# Carrier_Board.net
KiCad netlist of a schematic drawn in EAGLE
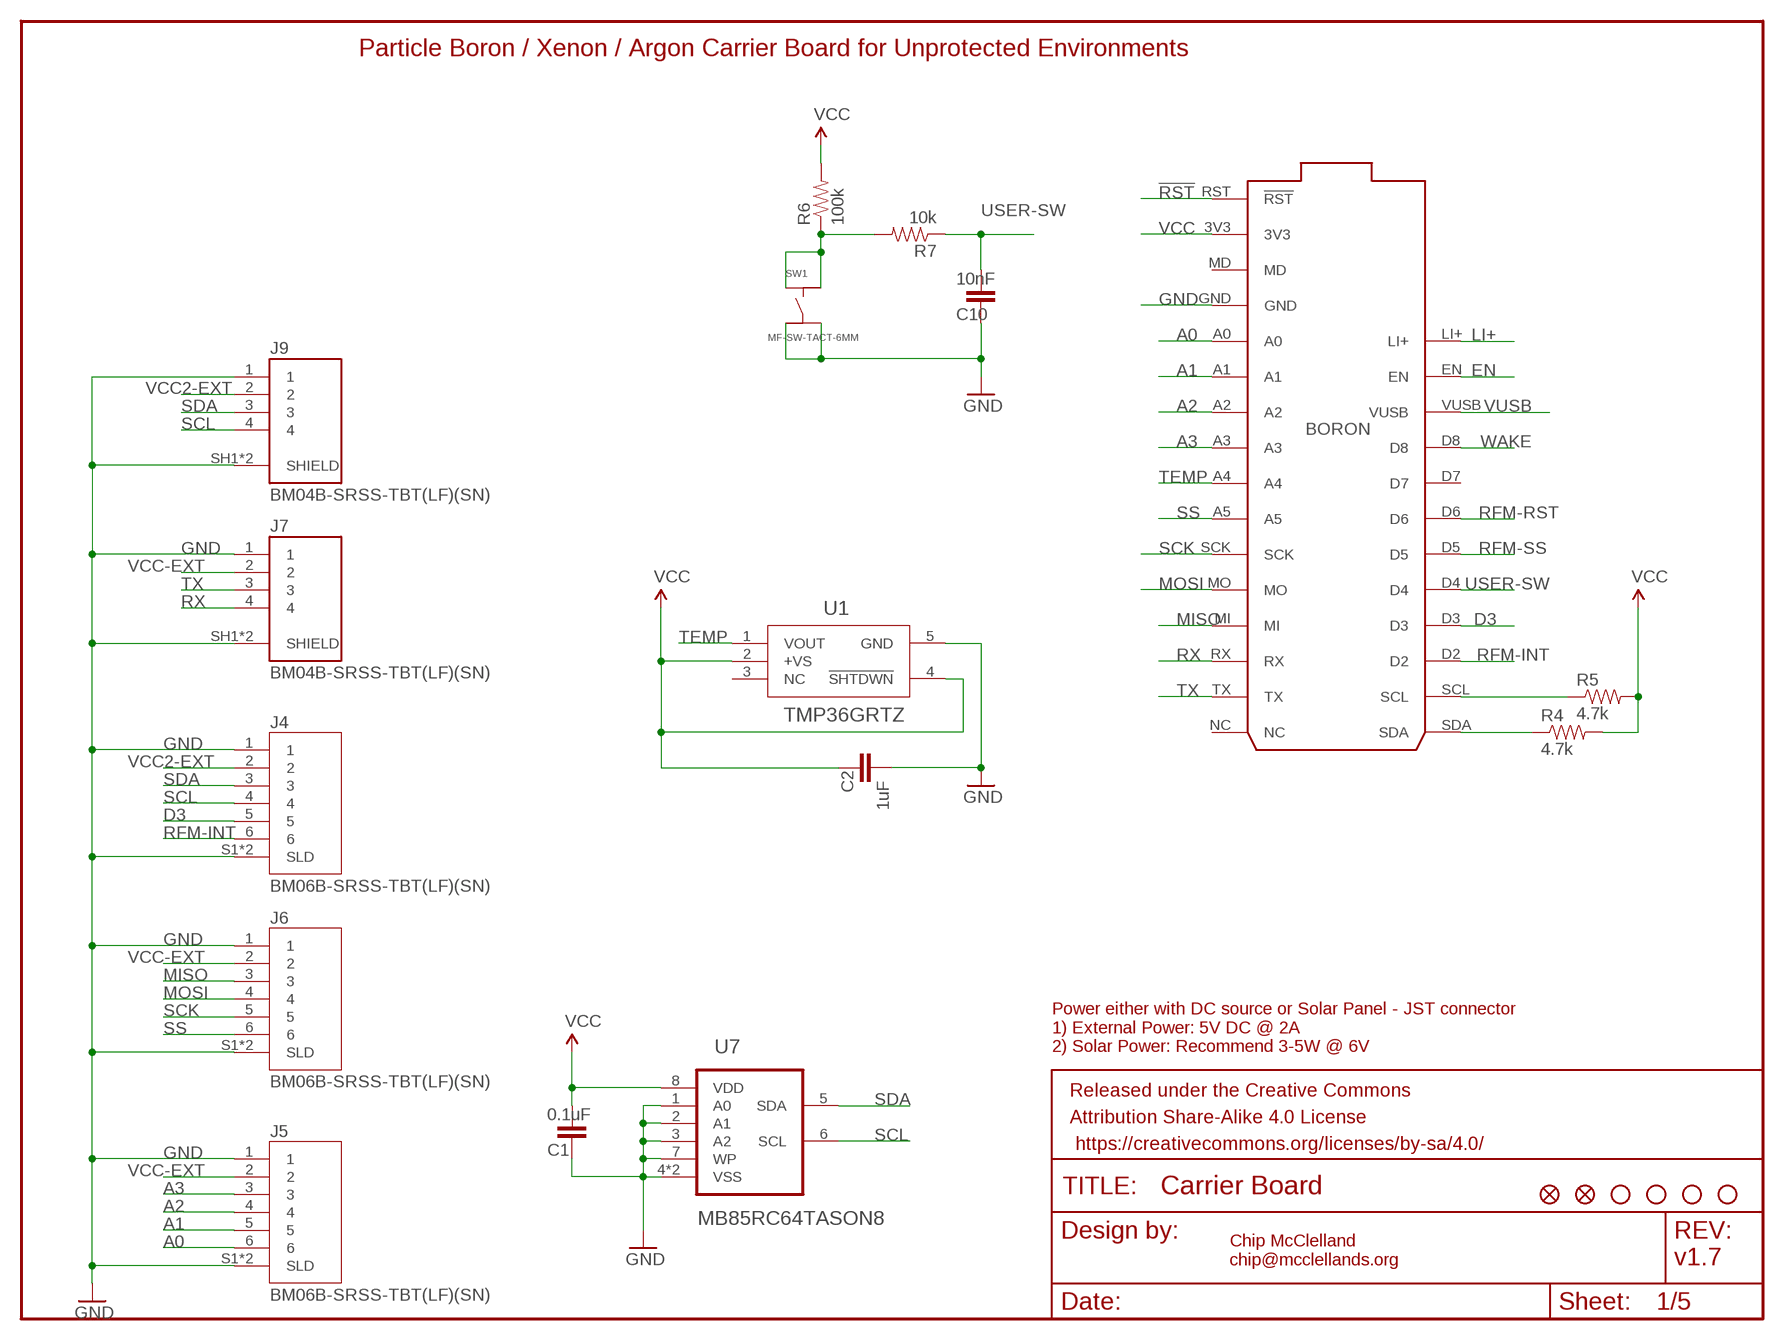
[diagram p0: schematic, sheet 1]
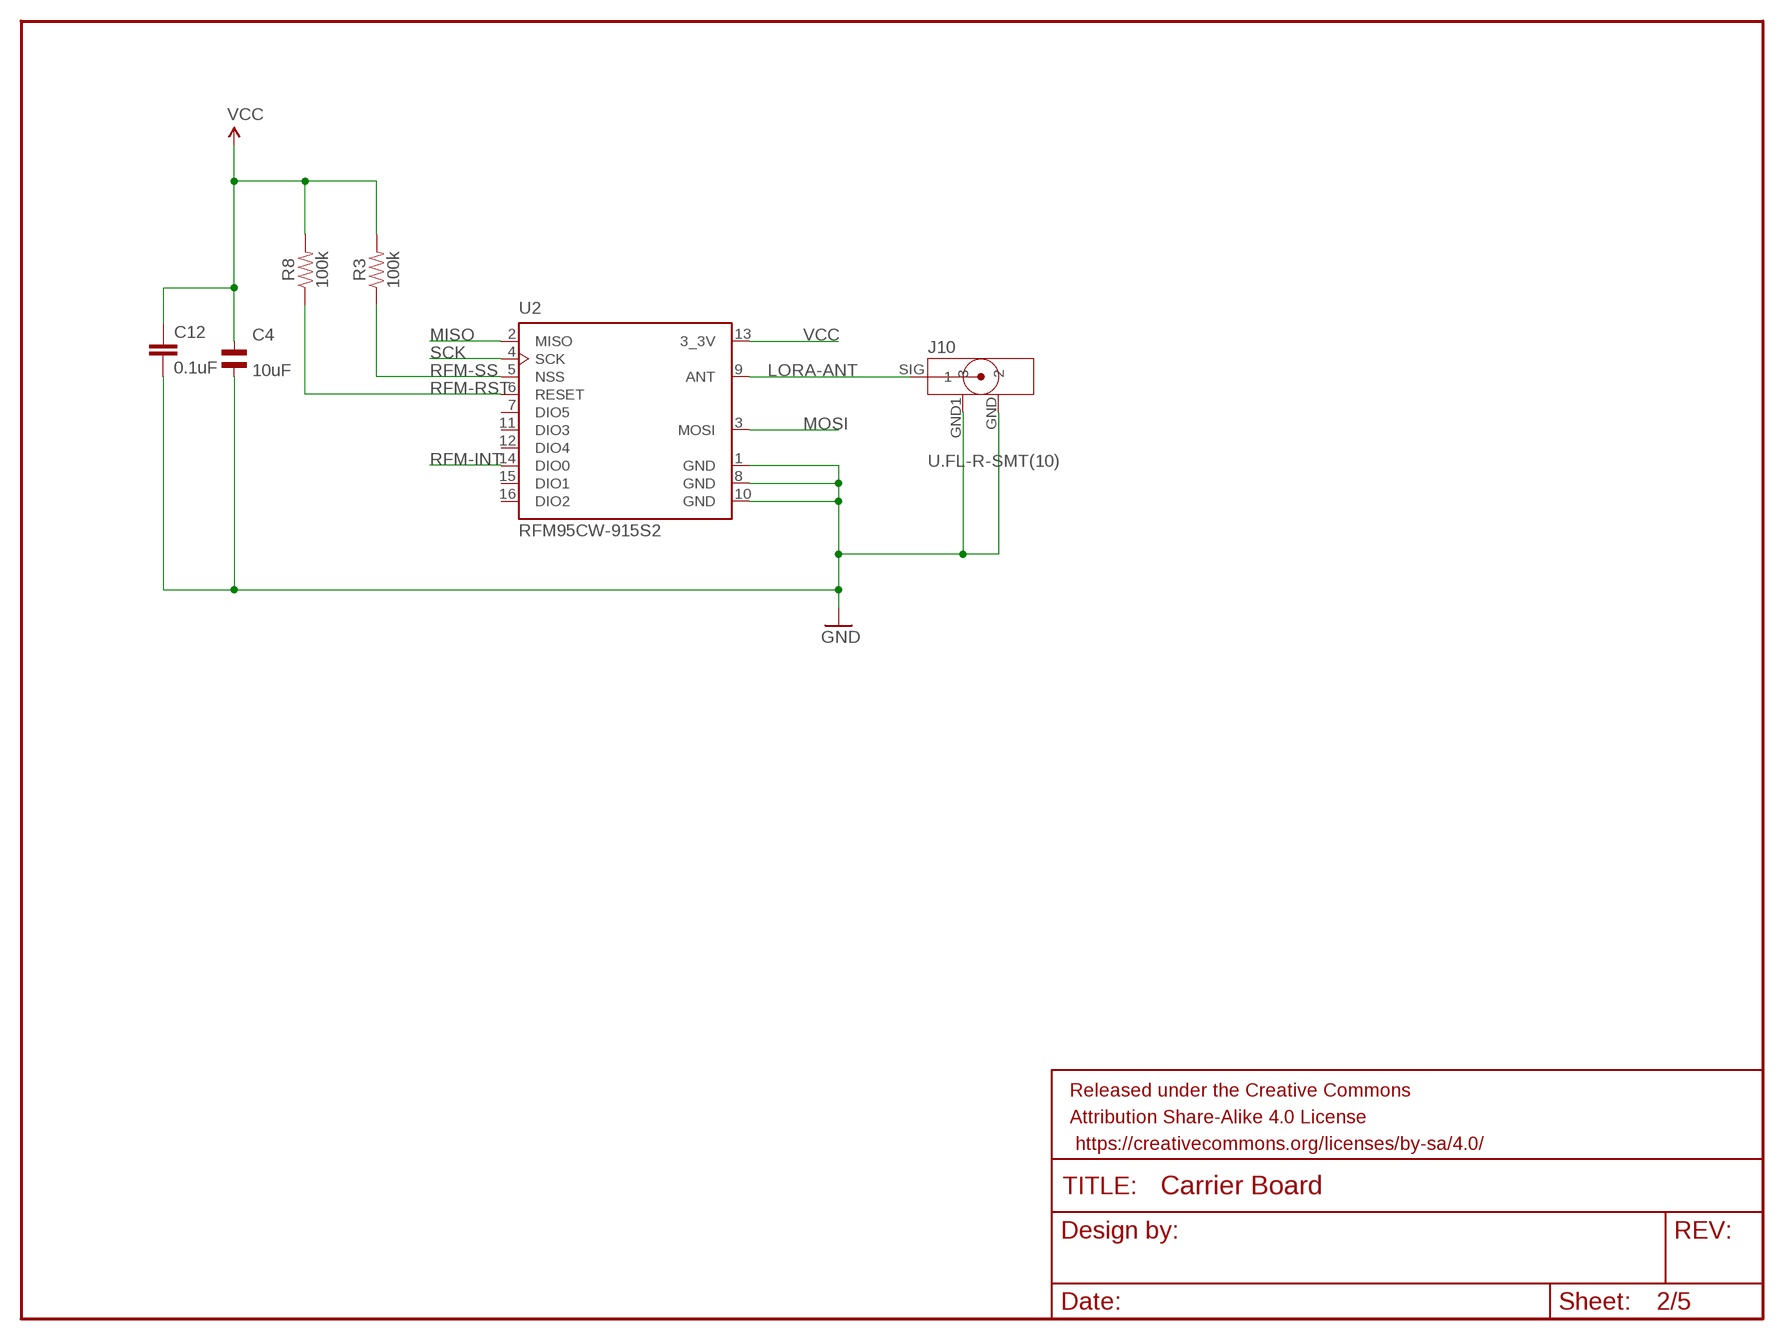
[diagram p1: schematic, sheet 2]
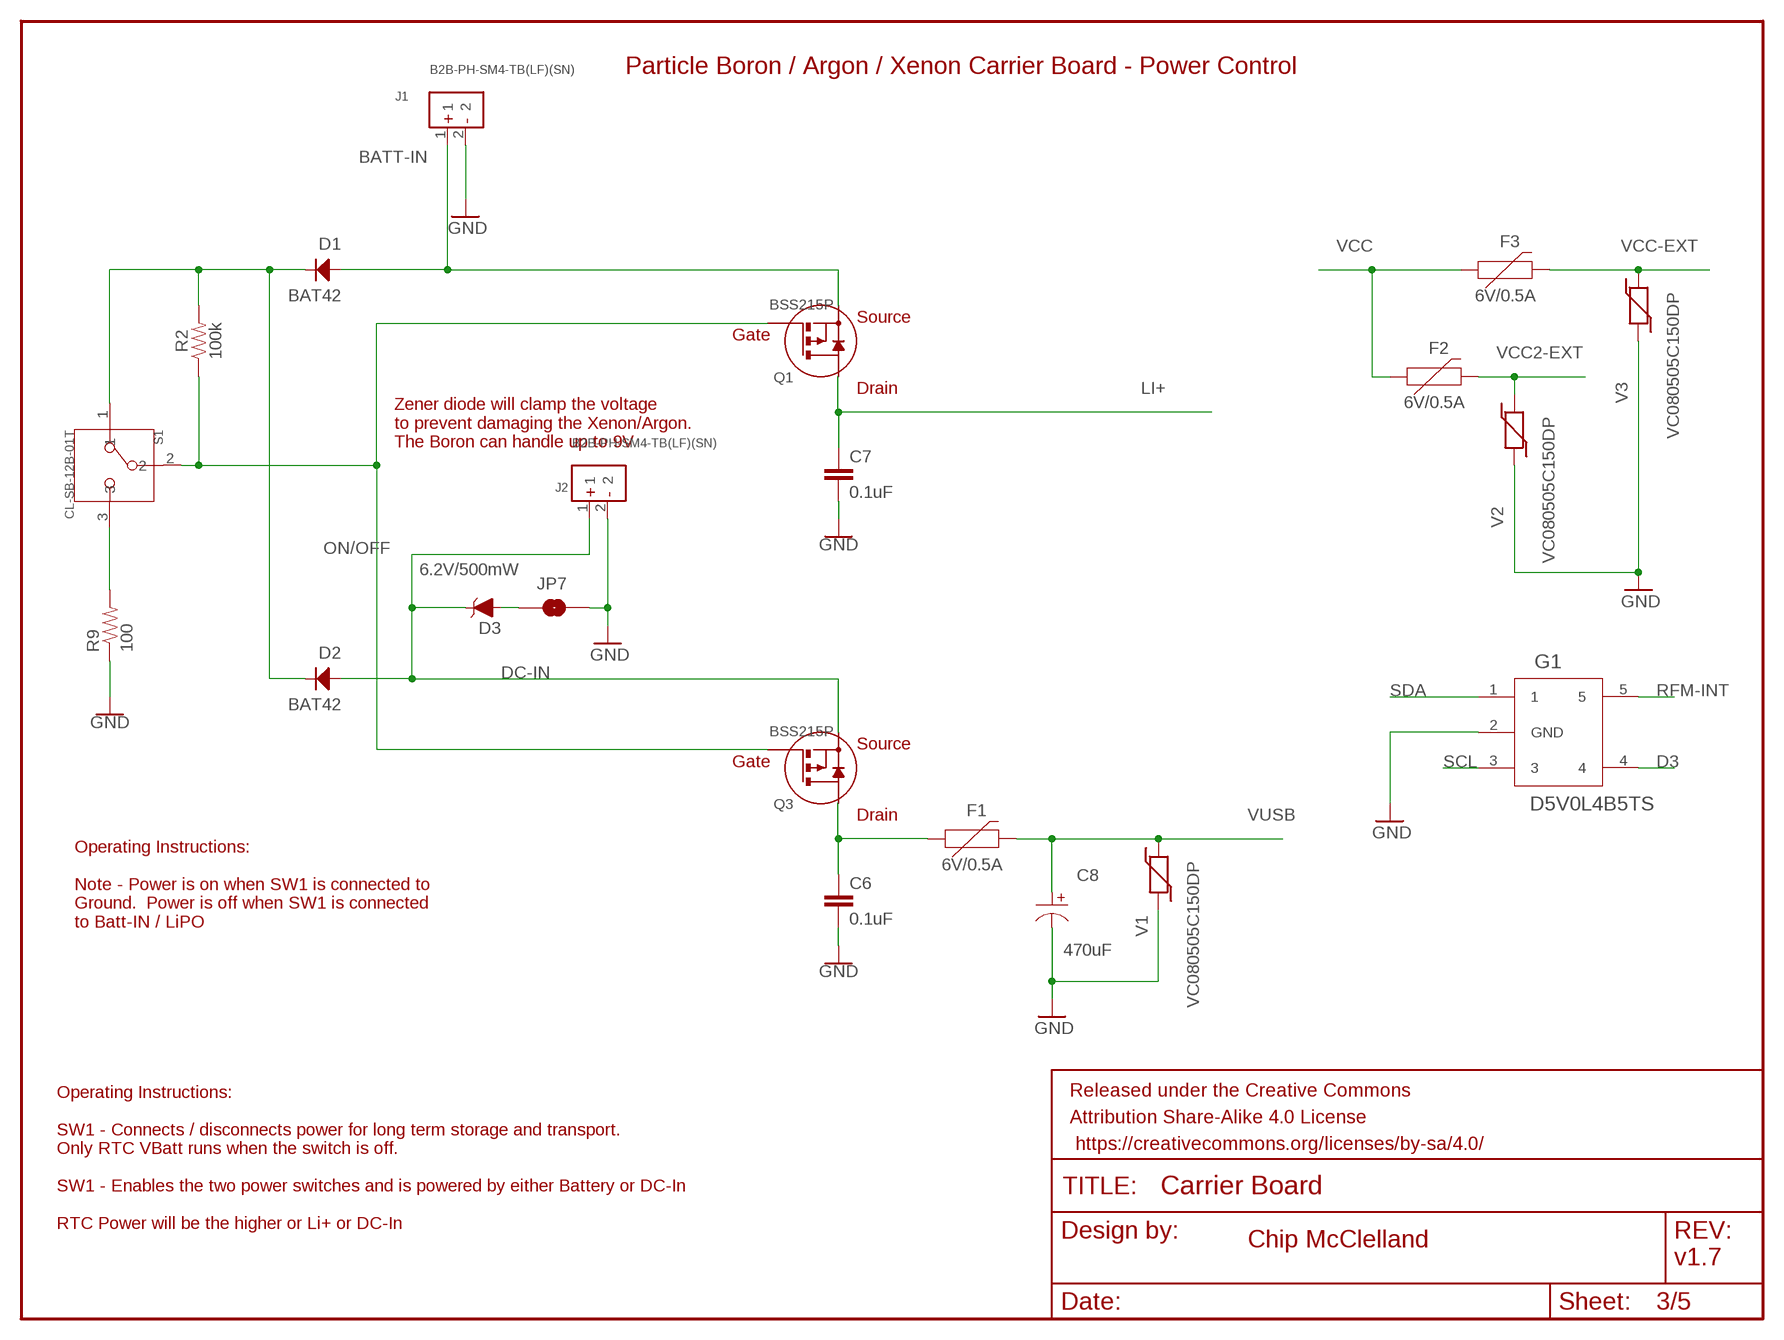
[diagram p2: schematic, sheet 3]
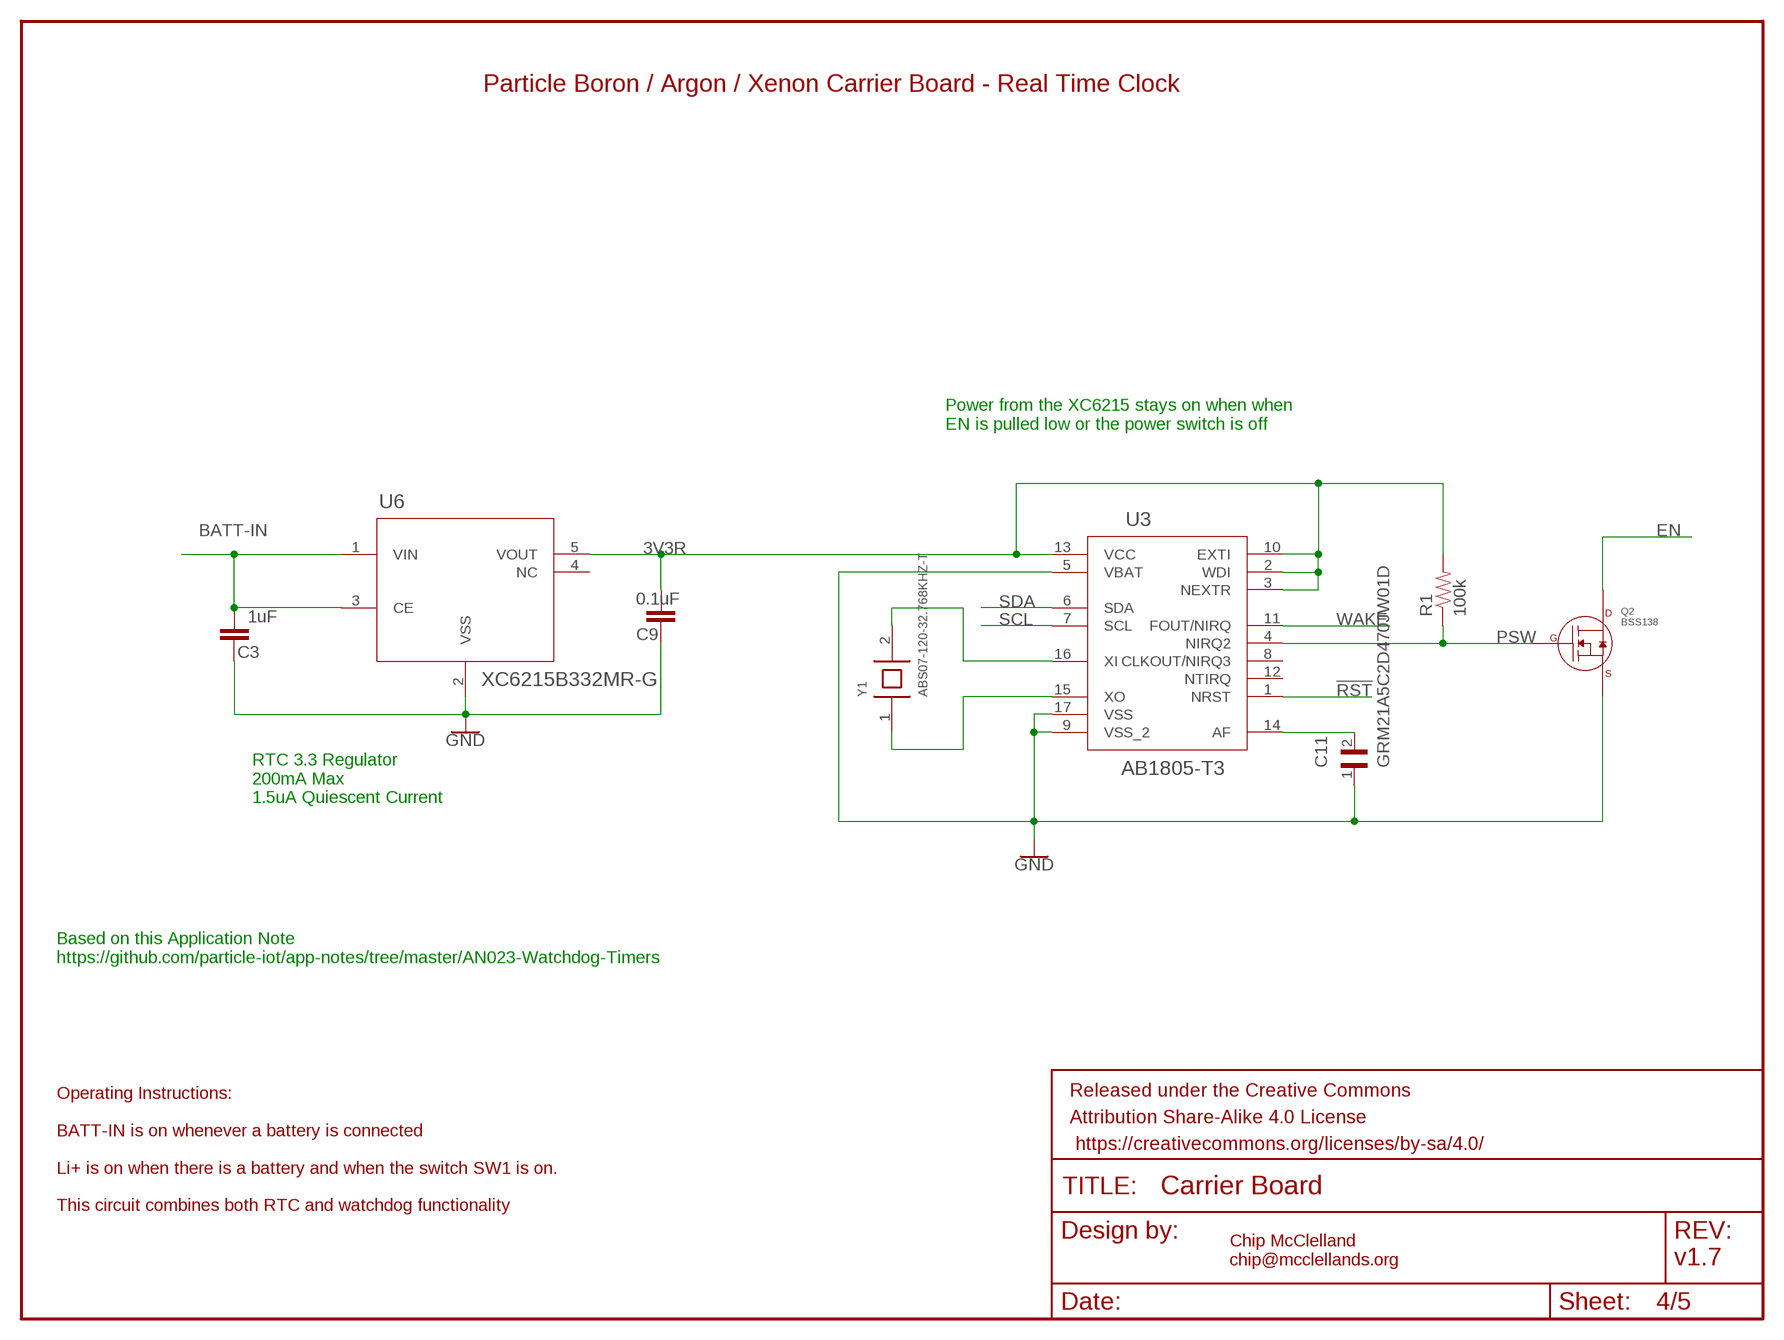
[diagram p3: schematic, sheet 4]
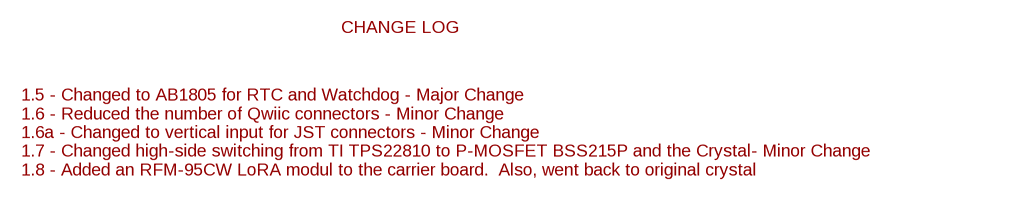
[diagram p4: schematic, sheet 5]

(export (version "E")
  (design (tool "Eeschema 10.0.6"))
  (components
    (comp (ref "C4")
      (value "10uF")
      (footprint "eagle-import:C1206")
      (fields
        (field (name "HOUSEPART") "Yes")
        (field (name "MPN") "MF-CAP-1206-10uF")
        (field (name "VOLTAGE") "16V")
      )
      (libsource (lib "eagle-import") (part "CAP-MF-10UF-1206"))
    )
    (comp (ref "C12")
      (value "0.1uF")
      (footprint "eagle-import:0805@1")
      (fields
        (field (name "HOUSEPART") "YES")
        (field (name "MPN") "MF-CAP-0805-0.1uF")
        (field (name "HOUSEPART_1") "Yes")
      )
      (libsource (lib "eagle-import") (part "CAP-MF-0.1UF-0805"))
    )
    (comp (ref "FRAME4")
      (value "FRAME-LETTERNO_PACKAGE")
      (footprint "eagle-import:DUMMY")
      (fields (field (name "DESIGNER") "Nobody"))
      (libsource (lib "eagle-import") (part "FRAME-LETTERNO_PACKAGE"))
    )
    (comp (ref "J10")
      (value "U.FL-R-SMT(10)")
      (footprint "eagle-import:U.FL-R-SMT(10)")
      (fields
        (field (name "DIGIKEY_PART_NUMBER") "H9161CT-ND")
        (field (name "MANUFACTURER") "Hirose Electric Co Ltd")
        (field (name "CREATED_BY") "PCBLayout.com")
      )
      (libsource (lib "eagle-import") (part "U.FL-R-SMT(10)"))
    )
    (comp (ref "R3")
      (value "100k")
      (footprint "eagle-import:0805")
      (fields (field (name "MPN") "MF-RES-0805-100K"))
      (libsource (lib "eagle-import") (part "RESISTOR-MF-100K-0805"))
    )
    (comp (ref "R8")
      (value "100k")
      (footprint "eagle-import:0805")
      (fields (field (name "MPN") "MF-RES-0805-100K"))
      (libsource (lib "eagle-import") (part "RESISTOR-MF-100K-0805"))
    )
    (comp (ref "U2")
      (value "RFM95CW-915S2")
      (footprint "eagle-import:XCVR_RFM95W-868S2")
      (fields (field (name "MF") "RF Solutions") (field (name "MP") "RFM95W-868S2"))
      (libsource (lib "eagle-import") (part "RFM95W-868S2"))
    )
    (comp (ref "C1")
      (value "0.1uF")
      (footprint "eagle-import:0805@1")
      (fields
        (field (name "HOUSEPART") "YES")
        (field (name "MPN") "MF-CAP-0805-0.1uF")
        (field (name "HOUSEPART_1") "YES")
        (field (name "MPN_1") "MF-CAP-0805-0.1uF")
        (field (name "POPULATE") "1")
      )
      (libsource (lib "eagle-import") (part "CAP-MF-0.1UF-0805"))
    )
    (comp (ref "C2")
      (value "1uF")
      (footprint "eagle-import:0805@1")
      (fields
        (field (name "HOUSEPART") "yes")
        (field (name "MPN") "MF-CAP-0805-1uF")
        (field (name "MPN_1") "MF-CAP-0805-1uF")
      )
      (libsource (lib "eagle-import") (part "CAP-MF-1UF-0805"))
    )
    (comp (ref "C10")
      (value "10nF")
      (footprint "eagle-import:0805@1")
      (fields
        (field (name "HOUSEPART") "NO")
        (field (name "MPN") "C0805X103K1RAC3316")
        (field (name "HOUSEPART_1") "No")
        (field (name "MPN_1") "08051C103K4T2A")
        (field (name "POPULATE") "1")
      )
      (libsource (lib "eagle-import") (part "CAP-10NF-0805"))
    )
    (comp (ref "FD1")
      (value "FIDUCIALUFIDUCIAL")
      (footprint "eagle-import:FIDUCIAL-MICRO")
      (libsource (lib "eagle-import") (part "FIDUCIALUFIDUCIAL"))
    )
    (comp (ref "FD2")
      (value "FIDUCIALUFIDUCIAL")
      (footprint "eagle-import:FIDUCIAL-MICRO")
      (libsource (lib "eagle-import") (part "FIDUCIALUFIDUCIAL"))
    )
    (comp (ref "FRAME1")
      (value "FRAME-LETTER")
      (footprint "eagle-import:CREATIVE_COMMONS")
      (fields (field (name "POPULATE") "0"))
      (libsource (lib "eagle-import") (part "FRAME-LETTER"))
    )
    (comp (ref "J4")
      (value "BM06B-SRSS-TBT(LF)(SN)")
      (footprint "eagle-import:JST_BM06B-SRSS-TB(LF)(SN)")
      (libsource (lib "eagle-import") (part "BM06B-SRSS-TBT(LF)(SN)"))
    )
    (comp (ref "J5")
      (value "BM06B-SRSS-TBT(LF)(SN)")
      (footprint "eagle-import:JST_BM06B-SRSS-TB(LF)(SN)")
      (libsource (lib "eagle-import") (part "BM06B-SRSS-TBT(LF)(SN)"))
    )
    (comp (ref "J6")
      (value "BM06B-SRSS-TBT(LF)(SN)")
      (footprint "eagle-import:JST_BM06B-SRSS-TB(LF)(SN)")
      (libsource (lib "eagle-import") (part "BM06B-SRSS-TBT(LF)(SN)"))
    )
    (comp (ref "J7")
      (value "BM04B-SRSS-TBT(LF)(SN)")
      (footprint "eagle-import:CONN_BM04B-SRSS-TBT(LF)(SN)")
      (fields (field (name "MF") "JST Sales"))
      (libsource (lib "eagle-import") (part "BM04B-SRSS-TBT(LF)(SN)"))
    )
    (comp (ref "J9")
      (value "BM04B-SRSS-TBT(LF)(SN)")
      (footprint "eagle-import:CONN_BM04B-SRSS-TBT(LF)(SN)")
      (fields (field (name "MF") "JST Sales"))
      (libsource (lib "eagle-import") (part "BM04B-SRSS-TBT(LF)(SN)"))
    )
    (comp (ref "JP3")
      (value "STAND-OFF")
      (footprint "eagle-import:STAND-OFF")
      (libsource (lib "eagle-import") (part "STAND-OFF"))
    )
    (comp (ref "JP4")
      (value "STAND-OFF")
      (footprint "eagle-import:STAND-OFF")
      (libsource (lib "eagle-import") (part "STAND-OFF"))
    )
    (comp (ref "JP5")
      (value "STAND-OFF")
      (footprint "eagle-import:STAND-OFF")
      (libsource (lib "eagle-import") (part "STAND-OFF"))
    )
    (comp (ref "JP6")
      (value "STAND-OFF")
      (footprint "eagle-import:STAND-OFF")
      (libsource (lib "eagle-import") (part "STAND-OFF"))
    )
    (comp (ref "P1")
      (value "Particle Boron / Xenon / Argon")
      (footprint "eagle-import:PARTICLE-DEVICES_BORON")
      (libsource (lib "eagle-import") (part "PARTICLE-DEVICES-BORON"))
    )
    (comp (ref "R4")
      (value "4.7k")
      (footprint "eagle-import:0805")
      (fields
        (field (name "HOUSEPART") "1")
        (field (name "MPN") "MF-RES-0805-4.7K")
        (field (name "MPN_1") "MF-RES-0805-4.7K")
      )
      (libsource (lib "eagle-import") (part "RESISTOR-MF-4.7K-0805"))
    )
    (comp (ref "R5")
      (value "4.7k")
      (footprint "eagle-import:0805")
      (fields
        (field (name "HOUSEPART") "1")
        (field (name "MPN") "MF-RES-0805-4.7K")
        (field (name "MPN_1") "MF-RES-0805-4.7K")
      )
      (libsource (lib "eagle-import") (part "RESISTOR-MF-4.7K-0805"))
    )
    (comp (ref "R6")
      (value "100k")
      (footprint "eagle-import:0805")
      (fields
        (field (name "MPN") "MF-RES-0805-100K")
        (field (name "HOUSEPART") "YES")
        (field (name "MPN_1") "MF-RES-0805-100K")
      )
      (libsource (lib "eagle-import") (part "RESISTOR-MF-100K-0805"))
    )
    (comp (ref "R7")
      (value "10k")
      (footprint "eagle-import:0805")
      (fields
        (field (name "MPN") "MF-RES-0805-10K")
        (field (name "HOUSEPART") "YES")
        (field (name "MPN_1") "MF-RES-0805-10K")
      )
      (libsource (lib "eagle-import") (part "RESISTOR-MF-10K-0805"))
    )
    (comp (ref "SW1")
      (value "MF-SW-TACT-6MM")
      (footprint "eagle-import:TACT6MM")
      (fields (field (name "HOUSEPART") "YES"))
      (libsource (lib "eagle-import") (part "TACT_6MM"))
    )
    (comp (ref "U1")
      (value "TMP36GRTZ")
      (footprint "eagle-import:RJ_5_ADI")
      (fields
        (field (name "MANUFACTURER_PART_NUMBER") "TMP36GRTZ-REEL7")
        (field (name "MANUFACTURER_PART_NUMBER_1") "TMP36GRTZ-REEL7")
      )
      (libsource (lib "eagle-import") (part "TMP36GRTZ-REEL7"))
    )
    (comp (ref "U7")
      (value "MB85RC64TASON8")
      (footprint "eagle-import:SON50P200X300X75-9N")
      (libsource (lib "eagle-import") (part "MB85RC64TASON8"))
    )
    (comp (ref "C6")
      (value "0.1uF")
      (footprint "eagle-import:0805@1")
      (fields
        (field (name "HOUSEPART") "YES")
        (field (name "MPN") "MF-CAP-0805-0.1uF")
        (field (name "HOUSEPART_1") "Yes")
        (field (name "MPN_1") "MF-CAP-0805-0.1uF")
      )
      (libsource (lib "eagle-import") (part "CAP-MF-0.1UF-0805"))
    )
    (comp (ref "C7")
      (value "0.1uF")
      (footprint "eagle-import:0805@1")
      (fields
        (field (name "HOUSEPART") "YES")
        (field (name "MPN") "MF-CAP-0805-0.1uF")
        (field (name "HOUSEPART_1") "Yes")
        (field (name "MPN_1") "MF-CAP-0805-0.1uF")
      )
      (libsource (lib "eagle-import") (part "CAP-MF-0.1UF-0805"))
    )
    (comp (ref "C8")
      (value "470uF")
      (footprint "eagle-import:CP10MM")
      (fields (field (name "HOUSEPART") "1") (field (name "MPN") "MF-CAP-10MM-470uF"))
      (libsource (lib "eagle-import") (part "CAPACITOR_P_10MM"))
    )
    (comp (ref "D1")
      (value "BAT42")
      (footprint "eagle-import:SOD-123")
      (fields (field (name "HOUSEPART") "YES") (field (name "MPN") "MF-DIO-SOD123-BAT42"))
      (libsource (lib "eagle-import") (part "DIODES_SOD-123_BAT42"))
    )
    (comp (ref "D2")
      (value "BAT42")
      (footprint "eagle-import:SOD-123")
      (fields (field (name "HOUSEPART") "YES") (field (name "MPN") "MF-DIO-SOD123-BAT42"))
      (libsource (lib "eagle-import") (part "DIODES_SOD-123_BAT42"))
    )
    (comp (ref "D3")
      (value "6.2V/500mW")
      (footprint "eagle-import:PANASONIC_SMINI2-F5-B")
      (fields (field (name "MPN") "TDZ6V2J,115"))
      (libsource (lib "eagle-import") (part "DIODE-ZENER-DZ2J150M0L"))
    )
    (comp (ref "F1")
      (value "6V/0.5A")
      (footprint "eagle-import:1206")
      (fields (field (name "MPN") "046801.5NR"))
      (libsource (lib "eagle-import") (part "PPTC_HALF-AMP"))
    )
    (comp (ref "F2")
      (value "6V/0.5A")
      (footprint "eagle-import:1206")
      (fields (field (name "MPN") "0466.500NR"))
      (libsource (lib "eagle-import") (part "PPTC_HALF-AMP"))
    )
    (comp (ref "F3")
      (value "6V/0.5A")
      (footprint "eagle-import:1206")
      (fields (field (name "MPN") "0466.500NR"))
      (libsource (lib "eagle-import") (part "PPTC_HALF-AMP"))
    )
    (comp (ref "FRAME2")
      (value "FRAME-LETTER")
      (footprint "eagle-import:CREATIVE_COMMONS")
      (fields (field (name "POPULATE") "0"))
      (libsource (lib "eagle-import") (part "FRAME-LETTER"))
    )
    (comp (ref "G1")
      (value "D5V0L4B5TS")
      (footprint "eagle-import:SOT-23-5")
      (fields (field (name "MPN") "D5V0L4B5TS-7"))
      (libsource (lib "eagle-import") (part "D5V0L4B5TS"))
    )
    (comp (ref "J1")
      (value "B2B-PH-SM4-TB(LF)(SN)")
      (footprint "eagle-import:JST_B2B-PH-SM4-TB(LF)(SN)")
      (fields (field (name "DIGI-KEY_PART_NUMBER") "455-1734-1-ND") (field (name "MF") "JST Sales"))
      (libsource (lib "eagle-import") (part "B2B-PH-SM4-TB(LF)(SN)"))
    )
    (comp (ref "J2")
      (value "B2B-PH-SM4-TB(LF)(SN)")
      (footprint "eagle-import:JST_B2B-PH-SM4-TB(LF)(SN)")
      (fields (field (name "DIGI-KEY_PART_NUMBER") "455-1734-1-ND") (field (name "MF") "JST Sales"))
      (libsource (lib "eagle-import") (part "B2B-PH-SM4-TB(LF)(SN)"))
    )
    (comp (ref "JP7")
      (value "JUMPER-SMT_2_NO_SILK")
      (footprint "eagle-import:SMT-JUMPER_2_NO_SILK")
      (libsource (lib "eagle-import") (part "JUMPER-SMT_2_NO_SILK"))
    )
    (comp (ref "Q1")
      (value "BSS215P")
      (footprint "eagle-import:SOT-23_3L_ONS-M")
      (fields (field (name "HOUSEPART") "No") (field (name "MPN") "BSS215PH6327XTSA1"))
      (libsource (lib "eagle-import") (part "BSS215P"))
    )
    (comp (ref "Q3")
      (value "BSS215P")
      (footprint "eagle-import:SOT-23_3L_ONS-M")
      (fields (field (name "HOUSEPART") "No") (field (name "MPN") "BSS215PH6327XTSA1"))
      (libsource (lib "eagle-import") (part "BSS215P"))
    )
    (comp (ref "R2")
      (value "100k")
      (footprint "eagle-import:0805")
      (fields (field (name "MPN") "MF-RES-0805-100K"))
      (libsource (lib "eagle-import") (part "RESISTOR-MF-100K-0805"))
    )
    (comp (ref "R9")
      (value "100")
      (footprint "eagle-import:0805")
      (fields
        (field (name "HOUSEPART") "YES")
        (field (name "MPN") "MF-RES-0805-100")
        (field (name "HOUSEPART_1") "Yes")
        (field (name "MPN_1") "MF-RES-0805-100")
      )
      (libsource (lib "eagle-import") (part "RESISTOR-MF-100-0805"))
    )
    (comp (ref "S1")
      (value "CL-SB-12B-01T")
      (footprint "eagle-import:CL-SB-12B")
      (fields (field (name "DIGI-KEY_PART_NUMBER") "563-1318-1-ND") (field (name "MF") "Nidec Copal"))
      (libsource (lib "eagle-import") (part "CL-SB-12B-01T"))
    )
    (comp (ref "V1")
      (value "VC080505C150DP")
      (footprint "eagle-import:0805")
      (libsource (lib "eagle-import") (part "VARISTOR"))
    )
    (comp (ref "V2")
      (value "VC080505C150DP")
      (footprint "eagle-import:0805")
      (libsource (lib "eagle-import") (part "VARISTOR"))
    )
    (comp (ref "V3")
      (value "VC080505C150DP")
      (footprint "eagle-import:0805")
      (libsource (lib "eagle-import") (part "VARISTOR"))
    )
    (comp (ref "C3")
      (value "1uF")
      (footprint "eagle-import:0805@1")
      (fields
        (field (name "HOUSEPART") "yes")
        (field (name "MPN") "MF-CAP-0805-1uF")
        (field (name "MPN_1") "MF-CAP-0805-1uF")
      )
      (libsource (lib "eagle-import") (part "CAP-MF-1UF-0805"))
    )
    (comp (ref "C9")
      (value "0.1uF")
      (footprint "eagle-import:0805@1")
      (fields
        (field (name "HOUSEPART") "YES")
        (field (name "MPN") "MF-CAP-0805-0.1uF")
        (field (name "HOUSEPART_1") "YES")
        (field (name "MPN_1") "MF-CAP-0805-0.1uF")
        (field (name "POPULATE") "1")
      )
      (libsource (lib "eagle-import") (part "CAP-MF-0.1UF-0805"))
    )
    (comp (ref "C11")
      (value "GRM21A5C2D470JW01D")
      (footprint "eagle-import:CAPC2012X100N")
      (fields (field (name "DIGI-KEY_PART_NUMBER") "490-14653-1-ND") (field (name "MF") "Murata"))
      (libsource (lib "eagle-import") (part "GRM21A5C2D470JW01D"))
    )
    (comp (ref "FRAME3")
      (value "FRAME-LETTER")
      (footprint "eagle-import:CREATIVE_COMMONS")
      (fields (field (name "POPULATE") "0"))
      (libsource (lib "eagle-import") (part "FRAME-LETTER"))
    )
    (comp (ref "Q2")
      (value "BSS138")
      (footprint "eagle-import:SOT-23_3L_ONS")
      (fields
        (field (name "MPN") "MF-DSC-SOT233-BSS138")
        (field (name "COPYRIGHT") "Copyright (C) 2018 Accelerated Designs. All rights reserved")
      )
      (libsource (lib "eagle-import") (part "BSS138"))
    )
    (comp (ref "R1")
      (value "100k")
      (footprint "eagle-import:0805")
      (fields
        (field (name "MPN") "MF-RES-0805-100K")
        (field (name "HOUSEPART") "YES")
        (field (name "MPN_1") "MF-RES-0805-100K")
      )
      (libsource (lib "eagle-import") (part "RESISTOR-MF-100K-0805"))
    )
    (comp (ref "U3")
      (value "AB1805-T3")
      (footprint "eagle-import:QFN_16_ABR")
      (fields (field (name "MANUFACTURER") "Abracon LLC"))
      (libsource (lib "eagle-import") (part "AB1805-T3"))
    )
    (comp (ref "U6")
      (value "XC6215B332MR-G")
      (footprint "eagle-import:SOT-25_TOR")
      (libsource (lib "eagle-import") (part "XC6215B332MR-G"))
    )
    (comp (ref "Y1")
      (value "ABS07-120-32.768KHZ-T")
      (footprint "eagle-import:XTAL_ABS07-120-32.768KHZ-T")
      (fields
        (field (name "DIGI-KEY_PART_NUMBER") "535-11937-1-ND")
        (field (name "MF") "Abracon")
        (field (name "MPN") "ABS07-32.768KHZ-6-T")
      )
      (libsource (lib "eagle-import") (part "ABS07-120-32.768KHZ-T"))
    )
  )
  (nets
    (net (code "1") (name "3V3R") (class "Default")
      (node (ref "C9") (pin "1") (pinfunction "1_1") (pintype "passive"))
      (node (ref "R1") (pin "2") (pinfunction "2_2") (pintype "passive"))
      (node (ref "U3") (pin "10") (pinfunction "EXTI_10") (pintype "input"))
      (node (ref "U3") (pin "13") (pinfunction "VCC_13") (pintype "power_in"))
      (node (ref "U3") (pin "2") (pinfunction "WDI_2") (pintype "input"))
      (node (ref "U3") (pin "3") (pinfunction "NEXTR_3") (pintype "input"))
      (node (ref "U6") (pin "5") (pinfunction "VOUT_5") (pintype "output"))
    )
    (net (code "2") (name "A0") (class "Default")
      (node (ref "J5") (pin "6") (pinfunction "6_6") (pintype "passive"))
      (node (ref "P1") (pin "A0") (pinfunction "A0_A0") (pintype "bidirectional"))
    )
    (net (code "3") (name "A1") (class "Default")
      (node (ref "J5") (pin "5") (pinfunction "5_5") (pintype "passive"))
      (node (ref "P1") (pin "A1") (pinfunction "A1_A1") (pintype "bidirectional"))
    )
    (net (code "4") (name "A2") (class "Default")
      (node (ref "J5") (pin "4") (pinfunction "4_4") (pintype "passive"))
      (node (ref "P1") (pin "A2") (pinfunction "A2_A2") (pintype "bidirectional"))
    )
    (net (code "5") (name "A3") (class "Default")
      (node (ref "J5") (pin "3") (pinfunction "3_3") (pintype "passive"))
      (node (ref "P1") (pin "A3") (pinfunction "A3_A3") (pintype "bidirectional"))
    )
    (net (code "6") (name "BATT-IN") (class "Default")
      (node (ref "C3") (pin "2") (pinfunction "2_2") (pintype "passive"))
      (node (ref "D1") (pin "ANODE") (pinfunction "ANODE_ANODE") (pintype "bidirectional"))
      (node (ref "J1") (pin "1") (pinfunction "1_1") (pintype "passive"))
      (node (ref "Q1") (pin "2") (pinfunction "SOURCE_2") (pintype "passive"))
      (node (ref "U6") (pin "1") (pinfunction "VIN_1") (pintype "power_in"))
      (node (ref "U6") (pin "3") (pinfunction "CE_3") (pintype "passive"))
    )
    (net (code "7") (name "D3") (class "Default")
      (node (ref "G1") (pin "4") (pinfunction "4_4") (pintype "output"))
      (node (ref "J4") (pin "5") (pinfunction "5_5") (pintype "passive"))
      (node (ref "P1") (pin "D3") (pinfunction "D3_D3") (pintype "bidirectional"))
    )
    (net (code "8") (name "DC-IN") (class "Default")
      (node (ref "D2") (pin "ANODE") (pinfunction "ANODE_ANODE") (pintype "bidirectional"))
      (node (ref "D3") (pin "C") (pinfunction "C_C") (pintype "passive"))
      (node (ref "J2") (pin "1") (pinfunction "1_1") (pintype "passive"))
      (node (ref "Q3") (pin "2") (pinfunction "SOURCE_2") (pintype "passive"))
    )
    (net (code "9") (name "EN") (class "Default")
      (node (ref "P1") (pin "EN") (pinfunction "EN_EN") (pintype "bidirectional"))
      (node (ref "Q2") (pin "3") (pinfunction "DRAIN_3") (pintype "bidirectional"))
    )
    (net (code "10") (name "GND") (class "Default")
      (node (ref "C1") (pin "2") (pinfunction "2_2") (pintype "passive"))
      (node (ref "C10") (pin "2") (pinfunction "2_2") (pintype "passive"))
      (node (ref "C11") (pin "1") (pinfunction "1_1") (pintype "passive"))
      (node (ref "C12") (pin "2") (pinfunction "2_2") (pintype "passive"))
      (node (ref "C2") (pin "2") (pinfunction "2_2") (pintype "passive"))
      (node (ref "C3") (pin "1") (pinfunction "1_1") (pintype "passive"))
      (node (ref "C4") (pin "P$2") (pinfunction "P$2_P$2") (pintype "passive"))
      (node (ref "C6") (pin "2") (pinfunction "2_2") (pintype "passive"))
      (node (ref "C7") (pin "2") (pinfunction "2_2") (pintype "passive"))
      (node (ref "C8") (pin "P$2") (pinfunction "P$2_P$2") (pintype "passive"))
      (node (ref "C9") (pin "2") (pinfunction "2_2") (pintype "passive"))
      (node (ref "G1") (pin "2") (pinfunction "GND_2") (pintype "power_in"))
      (node (ref "J1") (pin "2") (pinfunction "2_2") (pintype "passive"))
      (node (ref "J10") (pin "GND") (pinfunction "2_GND") (pintype "passive"))
      (node (ref "J10") (pin "GND1") (pinfunction "3_GND1") (pintype "passive"))
      (node (ref "J2") (pin "2") (pinfunction "2_2") (pintype "passive"))
      (node (ref "J4") (pin "1") (pinfunction "1_1") (pintype "passive"))
      (node (ref "J4") (pin "S1") (pinfunction "SLD_S1") (pintype "passive"))
      (node (ref "J4") (pin "S2") (pinfunction "SLD_S2") (pintype "passive"))
      (node (ref "J5") (pin "1") (pinfunction "1_1") (pintype "passive"))
      (node (ref "J5") (pin "S1") (pinfunction "SLD_S1") (pintype "passive"))
      (node (ref "J5") (pin "S2") (pinfunction "SLD_S2") (pintype "passive"))
      (node (ref "J6") (pin "1") (pinfunction "1_1") (pintype "passive"))
      (node (ref "J6") (pin "S1") (pinfunction "SLD_S1") (pintype "passive"))
      (node (ref "J6") (pin "S2") (pinfunction "SLD_S2") (pintype "passive"))
      (node (ref "J7") (pin "1") (pinfunction "1_1") (pintype "passive"))
      (node (ref "J7") (pin "SH1") (pinfunction "SHIELD_SH1") (pintype "passive"))
      (node (ref "J7") (pin "SH2") (pinfunction "SHIELD_SH2") (pintype "passive"))
      (node (ref "J9") (pin "1") (pinfunction "1_1") (pintype "passive"))
      (node (ref "J9") (pin "SH1") (pinfunction "SHIELD_SH1") (pintype "passive"))
      (node (ref "J9") (pin "SH2") (pinfunction "SHIELD_SH2") (pintype "passive"))
      (node (ref "JP7") (pin "1") (pinfunction "1_1") (pintype "passive"))
      (node (ref "P1") (pin "GND") (pinfunction "GND_GND") (pintype "bidirectional"))
      (node (ref "Q2") (pin "2") (pinfunction "SOURCE_2") (pintype "bidirectional"))
      (node (ref "R9") (pin "1") (pinfunction "1_1") (pintype "passive"))
      (node (ref "SW1") (pin "P$3") (pinfunction "P$3_P$3") (pintype "bidirectional"))
      (node (ref "SW1") (pin "P$4") (pinfunction "P$4_P$4") (pintype "bidirectional"))
      (node (ref "U1") (pin "5") (pinfunction "GND_5") (pintype "passive"))
      (node (ref "U2") (pin "1") (pinfunction "GND_1") (pintype "power_in"))
      (node (ref "U2") (pin "10") (pinfunction "GND_10") (pintype "power_in"))
      (node (ref "U2") (pin "8") (pinfunction "GND_8") (pintype "power_in"))
      (node (ref "U3") (pin "17") (pinfunction "VSS_17") (pintype "power_in"))
      (node (ref "U3") (pin "5") (pinfunction "VBAT_5") (pintype "power_in"))
      (node (ref "U3") (pin "9") (pinfunction "VSS_2_9") (pintype "power_in"))
      (node (ref "U6") (pin "2") (pinfunction "VSS_2") (pintype "passive"))
      (node (ref "U7") (pin "1") (pinfunction "A0_1") (pintype "input"))
      (node (ref "U7") (pin "2") (pinfunction "A1_2") (pintype "input"))
      (node (ref "U7") (pin "3") (pinfunction "A2_3") (pintype "input"))
      (node (ref "U7") (pin "4") (pinfunction "VSS_4") (pintype "passive"))
      (node (ref "U7") (pin "7") (pinfunction "WP_7") (pintype "input"))
      (node (ref "U7") (pin "9") (pinfunction "VSS_9") (pintype "passive"))
      (node (ref "V1") (pin "1") (pinfunction "1_1") (pintype "passive"))
      (node (ref "V2") (pin "1") (pinfunction "1_1") (pintype "passive"))
      (node (ref "V3") (pin "1") (pinfunction "1_1") (pintype "passive"))
    )
    (net (code "11") (name "LI+") (class "Default")
      (node (ref "C7") (pin "1") (pinfunction "1_1") (pintype "passive"))
      (node (ref "P1") (pin "LI+") (pinfunction "LI+_LI+") (pintype "bidirectional"))
      (node (ref "Q1") (pin "3") (pinfunction "DRAIN_3") (pintype "passive"))
    )
    (net (code "12") (name "LORA-ANT") (class "Default")
      (node (ref "J10") (pin "SIG") (pinfunction "1_SIG") (pintype "passive"))
      (node (ref "U2") (pin "9") (pinfunction "ANT_9") (pintype "passive"))
    )
    (net (code "13") (name "MISO") (class "Default")
      (node (ref "J6") (pin "3") (pinfunction "3_3") (pintype "passive"))
      (node (ref "P1") (pin "MI") (pinfunction "MI_MI") (pintype "bidirectional"))
      (node (ref "U2") (pin "2") (pinfunction "MISO_2") (pintype "input"))
    )
    (net (code "14") (name "MOSI") (class "Default")
      (node (ref "J6") (pin "4") (pinfunction "4_4") (pintype "passive"))
      (node (ref "P1") (pin "MO") (pinfunction "MO_MO") (pintype "bidirectional"))
      (node (ref "U2") (pin "3") (pinfunction "MOSI_3") (pintype "output"))
    )
    (net (code "15") (name "Net-(D1-PadCATHODE)") (class "Default")
      (node (ref "D1") (pin "CATHODE") (pinfunction "CATHODE_CATHODE") (pintype "bidirectional"))
      (node (ref "D2") (pin "CATHODE") (pinfunction "CATHODE_CATHODE") (pintype "bidirectional"))
      (node (ref "R2") (pin "2") (pinfunction "2_2") (pintype "passive"))
      (node (ref "S1") (pin "1") (pinfunction "1_1") (pintype "bidirectional"))
    )
    (net (code "16") (name "Net-(D3-PadA)") (class "Default")
      (node (ref "D3") (pin "A") (pinfunction "A_A") (pintype "passive"))
      (node (ref "JP7") (pin "2") (pinfunction "2_2") (pintype "passive"))
    )
    (net (code "17") (name "Net-(Q3-DRAIN)") (class "Default")
      (node (ref "C6") (pin "1") (pinfunction "1_1") (pintype "passive"))
      (node (ref "F1") (pin "1") (pinfunction "1_1") (pintype "bidirectional"))
      (node (ref "Q3") (pin "3") (pinfunction "DRAIN_3") (pintype "passive"))
    )
    (net (code "18") (name "Net-(R6-Pad1)") (class "Default")
      (node (ref "R6") (pin "1") (pinfunction "1_1") (pintype "passive"))
      (node (ref "R7") (pin "2") (pinfunction "2_2") (pintype "passive"))
      (node (ref "SW1") (pin "P$1") (pinfunction "P$1_P$1") (pintype "bidirectional"))
      (node (ref "SW1") (pin "P$2") (pinfunction "P$2_P$2") (pintype "bidirectional"))
    )
    (net (code "19") (name "Net-(R9-Pad2)") (class "Default")
      (node (ref "R9") (pin "2") (pinfunction "2_2") (pintype "passive"))
      (node (ref "S1") (pin "3") (pinfunction "3_3") (pintype "bidirectional"))
    )
    (net (code "20") (name "Net-(U3-AF)") (class "Default")
      (node (ref "C11") (pin "2") (pinfunction "2_2") (pintype "passive"))
      (node (ref "U3") (pin "14") (pinfunction "AF_14") (pintype "output"))
    )
    (net (code "21") (name "Net-(U3-XI)") (class "Default")
      (node (ref "U3") (pin "16") (pinfunction "XI_16") (pintype "input"))
      (node (ref "Y1") (pin "2") (pinfunction "2_2") (pintype "passive"))
    )
    (net (code "22") (name "Net-(U3-XO)") (class "Default")
      (node (ref "U3") (pin "15") (pinfunction "XO_15") (pintype "output"))
      (node (ref "Y1") (pin "1") (pinfunction "1_1") (pintype "passive"))
    )
    (net (code "23") (name "ON{slash}OFF") (class "Default")
      (node (ref "Q1") (pin "1") (pinfunction "GATE_1") (pintype "passive"))
      (node (ref "Q3") (pin "1") (pinfunction "GATE_1") (pintype "passive"))
      (node (ref "R2") (pin "1") (pinfunction "1_1") (pintype "passive"))
      (node (ref "S1") (pin "2") (pinfunction "2_2") (pintype "bidirectional"))
    )
    (net (code "24") (name "PSW") (class "Default")
      (node (ref "Q2") (pin "1") (pinfunction "GATE_1") (pintype "bidirectional"))
      (node (ref "R1") (pin "1") (pinfunction "1_1") (pintype "passive"))
      (node (ref "U3") (pin "4") (pinfunction "NIRQ2_4") (pintype "output"))
    )
    (net (code "25") (name "RFM-INT") (class "Default")
      (node (ref "G1") (pin "5") (pinfunction "5_5") (pintype "output"))
      (node (ref "J4") (pin "6") (pinfunction "6_6") (pintype "passive"))
      (node (ref "P1") (pin "D2") (pinfunction "D2_D2") (pintype "bidirectional"))
      (node (ref "U2") (pin "14") (pinfunction "DIO0_14") (pintype "bidirectional"))
    )
    (net (code "26") (name "RFM-RST") (class "Default")
      (node (ref "P1") (pin "D6") (pinfunction "D6_D6") (pintype "bidirectional"))
      (node (ref "R8") (pin "1") (pinfunction "1_1") (pintype "passive"))
      (node (ref "U2") (pin "6") (pinfunction "RESET_6") (pintype "bidirectional"))
    )
    (net (code "27") (name "RFM-SS") (class "Default")
      (node (ref "P1") (pin "D5") (pinfunction "D5_D5") (pintype "bidirectional"))
      (node (ref "R3") (pin "1") (pinfunction "1_1") (pintype "passive"))
      (node (ref "U2") (pin "5") (pinfunction "NSS_5") (pintype "input"))
    )
    (net (code "28") (name "RX") (class "Default")
      (node (ref "J7") (pin "4") (pinfunction "4_4") (pintype "passive"))
      (node (ref "P1") (pin "RX") (pinfunction "RX_RX") (pintype "bidirectional"))
    )
    (net (code "29") (name "SCK") (class "Default")
      (node (ref "J6") (pin "5") (pinfunction "5_5") (pintype "passive"))
      (node (ref "P1") (pin "SCK") (pinfunction "SCK_SCK") (pintype "bidirectional"))
      (node (ref "U2") (pin "4") (pinfunction "SCK_4") (pintype "input"))
    )
    (net (code "30") (name "SCL") (class "Default")
      (node (ref "G1") (pin "3") (pinfunction "3_3") (pintype "input"))
      (node (ref "J4") (pin "4") (pinfunction "4_4") (pintype "passive"))
      (node (ref "J9") (pin "4") (pinfunction "4_4") (pintype "passive"))
      (node (ref "P1") (pin "SCL") (pinfunction "SCL_SCL") (pintype "bidirectional"))
      (node (ref "R5") (pin "1") (pinfunction "1_1") (pintype "passive"))
      (node (ref "U3") (pin "7") (pinfunction "SCL_7") (pintype "input"))
      (node (ref "U7") (pin "6") (pinfunction "SCL_6") (pintype "input"))
    )
    (net (code "31") (name "SDA") (class "Default")
      (node (ref "G1") (pin "1") (pinfunction "1_1") (pintype "input"))
      (node (ref "J4") (pin "3") (pinfunction "3_3") (pintype "passive"))
      (node (ref "J9") (pin "3") (pinfunction "3_3") (pintype "passive"))
      (node (ref "P1") (pin "SDA") (pinfunction "SDA_SDA") (pintype "bidirectional"))
      (node (ref "R4") (pin "1") (pinfunction "1_1") (pintype "passive"))
      (node (ref "U3") (pin "6") (pinfunction "SDA_6") (pintype "bidirectional"))
      (node (ref "U7") (pin "5") (pinfunction "SDA_5") (pintype "bidirectional"))
    )
    (net (code "32") (name "SS") (class "Default")
      (node (ref "J6") (pin "6") (pinfunction "6_6") (pintype "passive"))
      (node (ref "P1") (pin "A5") (pinfunction "A5_A5") (pintype "bidirectional"))
    )
    (net (code "33") (name "TEMP") (class "Default")
      (node (ref "P1") (pin "A4") (pinfunction "A4_A4") (pintype "bidirectional"))
      (node (ref "U1") (pin "1") (pinfunction "VOUT_1") (pintype "passive"))
    )
    (net (code "34") (name "TX") (class "Default")
      (node (ref "J7") (pin "3") (pinfunction "3_3") (pintype "passive"))
      (node (ref "P1") (pin "TX") (pinfunction "TX_TX") (pintype "bidirectional"))
    )
    (net (code "35") (name "USER-SW") (class "Default")
      (node (ref "C10") (pin "1") (pinfunction "1_1") (pintype "passive"))
      (node (ref "P1") (pin "D4") (pinfunction "D4_D4") (pintype "bidirectional"))
      (node (ref "R7") (pin "1") (pinfunction "1_1") (pintype "passive"))
    )
    (net (code "36") (name "VCC") (class "Default")
      (node (ref "C1") (pin "1") (pinfunction "1_1") (pintype "passive"))
      (node (ref "C12") (pin "1") (pinfunction "1_1") (pintype "passive"))
      (node (ref "C2") (pin "1") (pinfunction "1_1") (pintype "passive"))
      (node (ref "C4") (pin "P$1") (pinfunction "P$1_P$1") (pintype "passive"))
      (node (ref "F2") (pin "1") (pinfunction "1_1") (pintype "bidirectional"))
      (node (ref "F3") (pin "1") (pinfunction "1_1") (pintype "bidirectional"))
      (node (ref "P1") (pin "3V3") (pinfunction "3V3_3V3") (pintype "bidirectional"))
      (node (ref "R3") (pin "2") (pinfunction "2_2") (pintype "passive"))
      (node (ref "R4") (pin "2") (pinfunction "2_2") (pintype "passive"))
      (node (ref "R5") (pin "2") (pinfunction "2_2") (pintype "passive"))
      (node (ref "R6") (pin "2") (pinfunction "2_2") (pintype "passive"))
      (node (ref "R8") (pin "2") (pinfunction "2_2") (pintype "passive"))
      (node (ref "U1") (pin "2") (pinfunction "+VS_2") (pintype "power_in"))
      (node (ref "U1") (pin "4") (pinfunction "~{SHTDWN}_4") (pintype "passive"))
      (node (ref "U2") (pin "13") (pinfunction "3_3V_13") (pintype "power_in"))
      (node (ref "U7") (pin "8") (pinfunction "VDD_8") (pintype "power_in"))
    )
    (net (code "37") (name "VCC-EXT") (class "Default")
      (node (ref "F3") (pin "2") (pinfunction "2_2") (pintype "bidirectional"))
      (node (ref "J5") (pin "2") (pinfunction "2_2") (pintype "passive"))
      (node (ref "J6") (pin "2") (pinfunction "2_2") (pintype "passive"))
      (node (ref "J7") (pin "2") (pinfunction "2_2") (pintype "passive"))
      (node (ref "V3") (pin "2") (pinfunction "2_2") (pintype "passive"))
    )
    (net (code "38") (name "VCC2-EXT") (class "Default")
      (node (ref "F2") (pin "2") (pinfunction "2_2") (pintype "bidirectional"))
      (node (ref "J4") (pin "2") (pinfunction "2_2") (pintype "passive"))
      (node (ref "J9") (pin "2") (pinfunction "2_2") (pintype "passive"))
      (node (ref "V2") (pin "2") (pinfunction "2_2") (pintype "passive"))
    )
    (net (code "39") (name "VUSB") (class "Default")
      (node (ref "C8") (pin "P$1") (pinfunction "P$1_P$1") (pintype "passive"))
      (node (ref "F1") (pin "2") (pinfunction "2_2") (pintype "bidirectional"))
      (node (ref "P1") (pin "VUSB") (pinfunction "VUSB_VUSB") (pintype "bidirectional"))
      (node (ref "V1") (pin "2") (pinfunction "2_2") (pintype "passive"))
    )
    (net (code "40") (name "WAKE") (class "Default")
      (node (ref "P1") (pin "D8") (pinfunction "D8_D8") (pintype "bidirectional"))
      (node (ref "U3") (pin "11") (pinfunction "FOUT/NIRQ_11") (pintype "output"))
    )
    (net (code "41") (name "unconnected-(P1-PadD7)") (class "Default")
      (node (ref "P1") (pin "D7") (pinfunction "D7_D7") (pintype "bidirectional"))
    )
    (net (code "42") (name "unconnected-(P1-PadMD)") (class "Default")
      (node (ref "P1") (pin "MD") (pinfunction "MD_MD") (pintype "bidirectional"))
    )
    (net (code "43") (name "unconnected-(P1-PadNC)") (class "Default")
      (node (ref "P1") (pin "NC") (pinfunction "NC_NC") (pintype "bidirectional"))
    )
    (net (code "44") (name "unconnected-(U1-NC-Pad3)") (class "Default")
      (node (ref "U1") (pin "3") (pinfunction "NC_3") (pintype "passive"))
    )
    (net (code "45") (name "unconnected-(U2-DIO1-Pad15)") (class "Default")
      (node (ref "U2") (pin "15") (pinfunction "DIO1_15") (pintype "bidirectional"))
    )
    (net (code "46") (name "unconnected-(U2-DIO2-Pad16)") (class "Default")
      (node (ref "U2") (pin "16") (pinfunction "DIO2_16") (pintype "bidirectional"))
    )
    (net (code "47") (name "unconnected-(U2-DIO3-Pad11)") (class "Default")
      (node (ref "U2") (pin "11") (pinfunction "DIO3_11") (pintype "bidirectional"))
    )
    (net (code "48") (name "unconnected-(U2-DIO4-Pad12)") (class "Default")
      (node (ref "U2") (pin "12") (pinfunction "DIO4_12") (pintype "bidirectional"))
    )
    (net (code "49") (name "unconnected-(U2-DIO5-Pad7)") (class "Default")
      (node (ref "U2") (pin "7") (pinfunction "DIO5_7") (pintype "bidirectional"))
    )
    (net (code "50") (name "unconnected-(U3-CLKOUT{slash}NIRQ3-Pad8)") (class "Default")
      (node (ref "U3") (pin "8") (pinfunction "CLKOUT/NIRQ3_8") (pintype "output"))
    )
    (net (code "51") (name "unconnected-(U3-NTIRQ-Pad12)") (class "Default")
      (node (ref "U3") (pin "12") (pinfunction "NTIRQ_12") (pintype "output"))
    )
    (net (code "52") (name "unconnected-(U6-NC-Pad4)") (class "Default")
      (node (ref "U6") (pin "4") (pinfunction "NC_4") (pintype "no_connect"))
    )
    (net (code "53") (name "~{RST}") (class "Default")
      (node (ref "P1") (pin "RST") (pinfunction "~{RST}_RST") (pintype "bidirectional"))
      (node (ref "U3") (pin "1") (pinfunction "NRST_1") (pintype "output"))
    )
  )
)
